# DM1098FFC_MIPI_CAM.net
KiCad netlist of a schematic drawn in Altium Designer
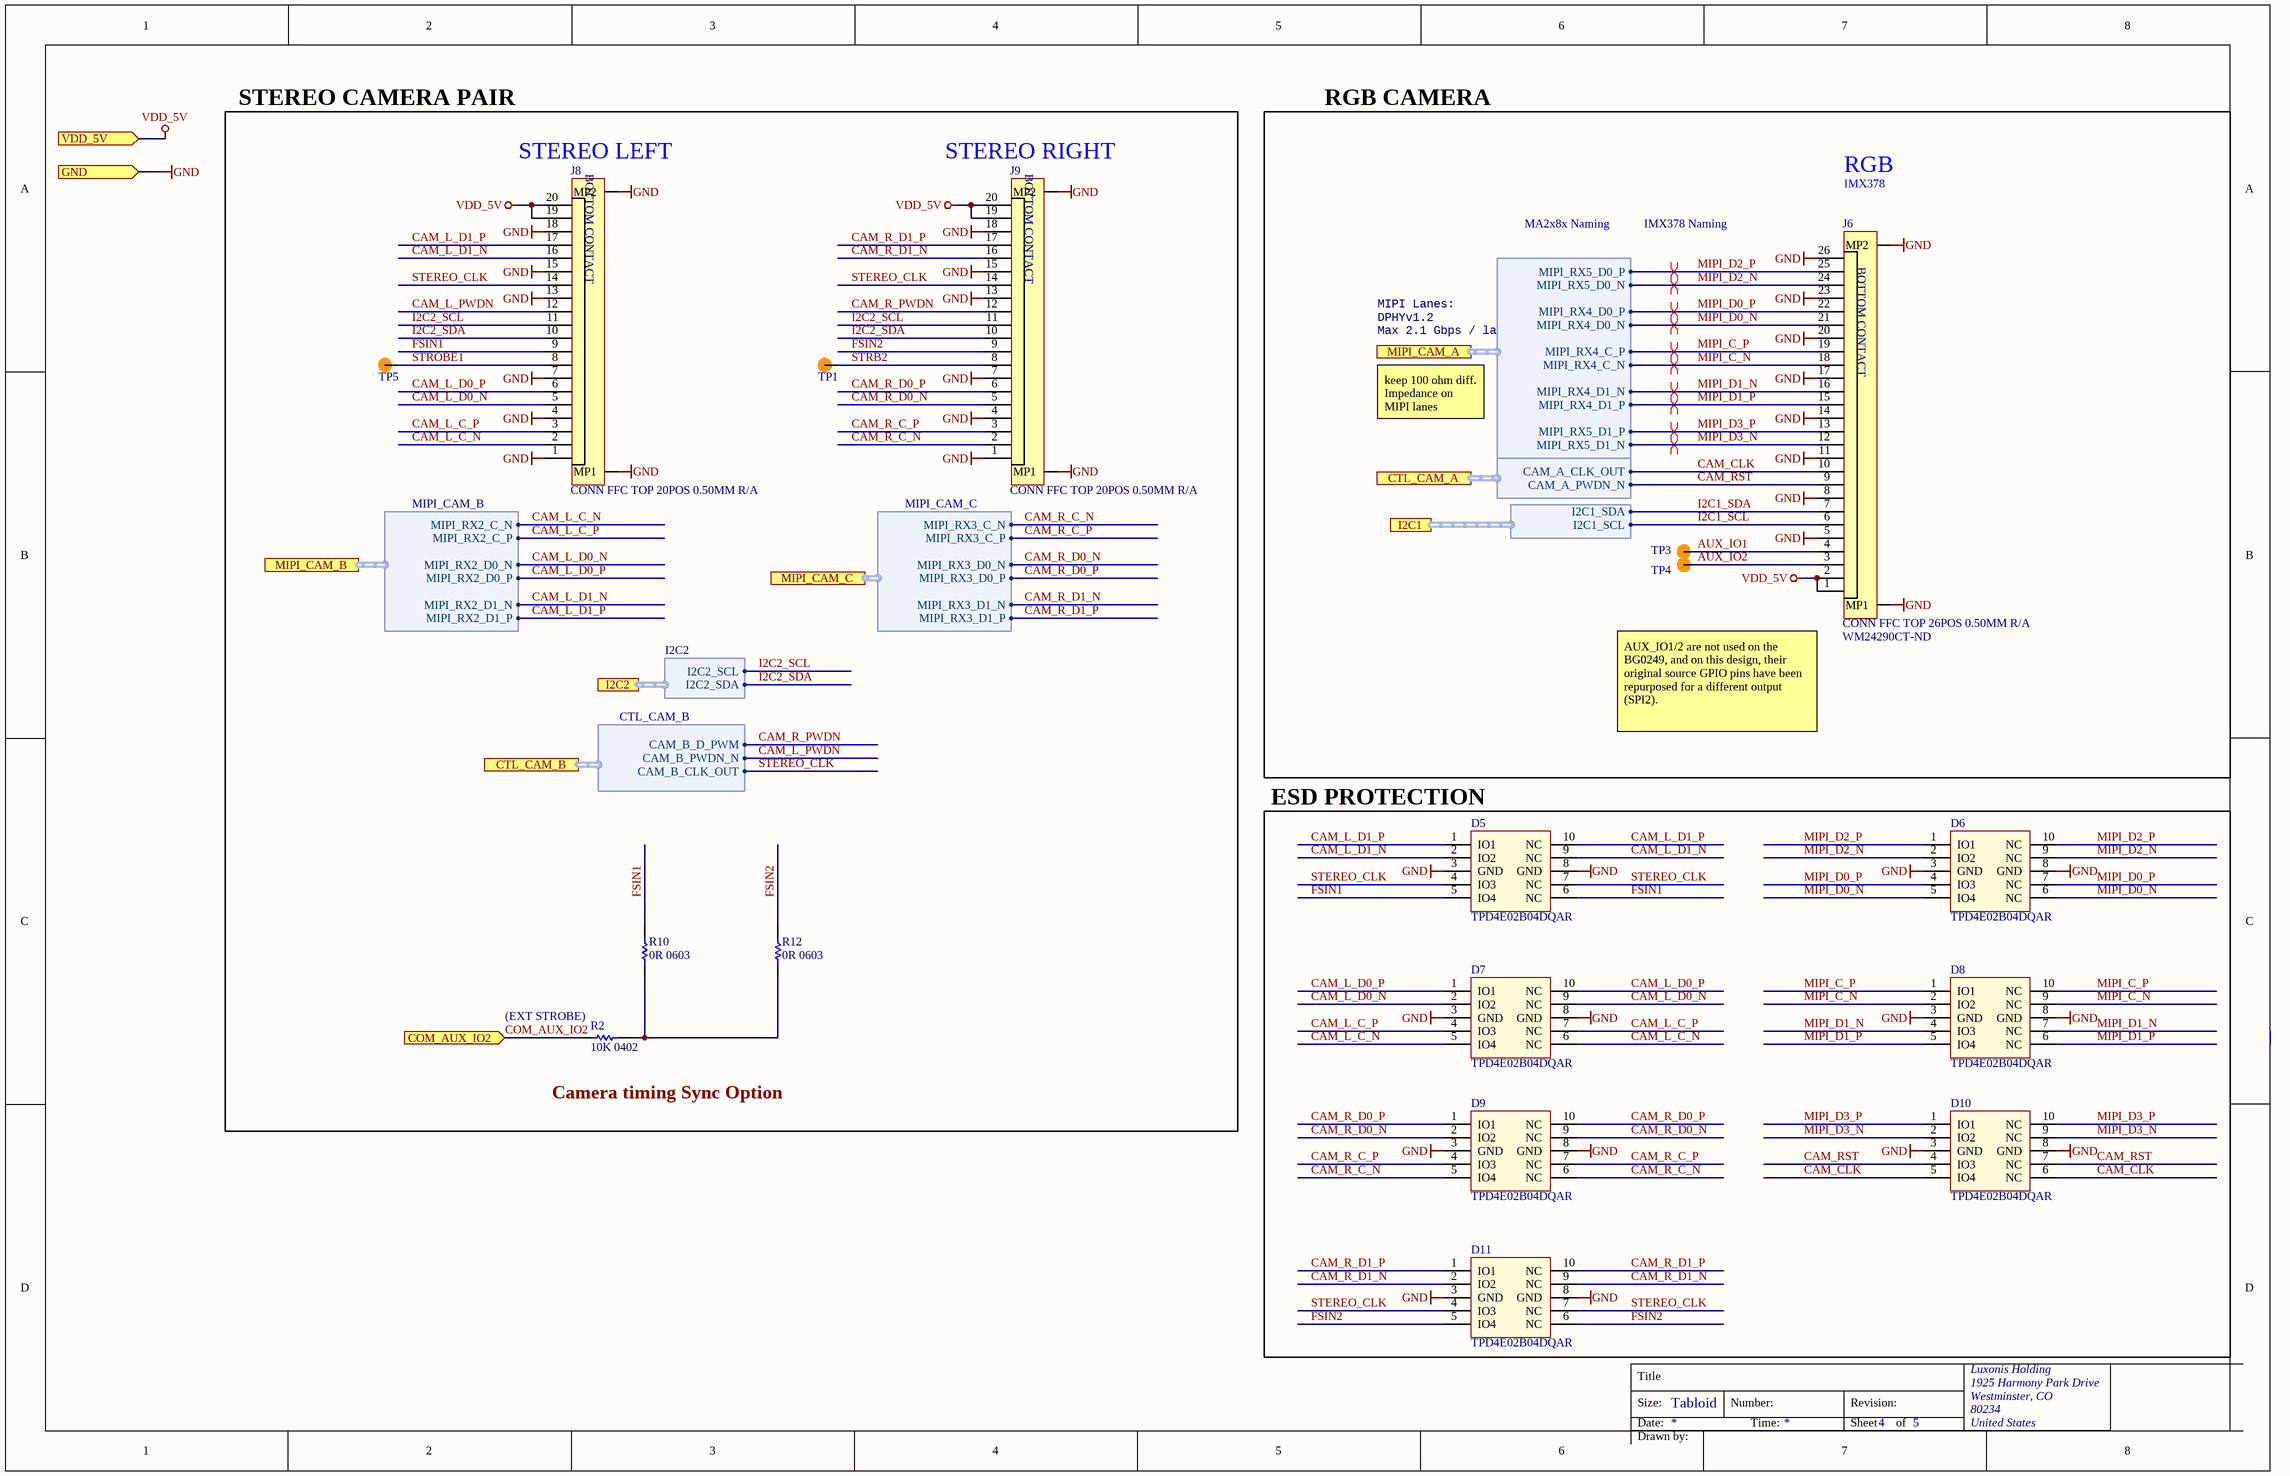
[diagram p0: DM1098FFC_MIPI_CAM.SchDoc]

(export (version "E")
  (design (tool "Eeschema 10.0.6"))
  (components
    (comp (ref "D5")
      (value "TPD4E02B04DQAR")
      (footprint "LuxonisMaster:TPD4E02B04DQAR")
      (libsource (lib "LuxonisMaster") (part "TPD4E02B04DQAR"))
    )
    (comp (ref "D6")
      (value "TPD4E02B04DQAR")
      (footprint "LuxonisMaster:TPD4E02B04DQAR")
      (libsource (lib "LuxonisMaster") (part "TPD4E02B04DQAR"))
    )
    (comp (ref "D7")
      (value "TPD4E02B04DQAR")
      (footprint "LuxonisMaster:TPD4E02B04DQAR")
      (libsource (lib "LuxonisMaster") (part "TPD4E02B04DQAR"))
    )
    (comp (ref "D8")
      (value "TPD4E02B04DQAR")
      (footprint "LuxonisMaster:TPD4E02B04DQAR")
      (libsource (lib "LuxonisMaster") (part "TPD4E02B04DQAR"))
    )
    (comp (ref "D9")
      (value "TPD4E02B04DQAR")
      (footprint "LuxonisMaster:TPD4E02B04DQAR")
      (libsource (lib "LuxonisMaster") (part "TPD4E02B04DQAR"))
    )
    (comp (ref "D10")
      (value "TPD4E02B04DQAR")
      (footprint "LuxonisMaster:TPD4E02B04DQAR")
      (libsource (lib "LuxonisMaster") (part "TPD4E02B04DQAR"))
    )
    (comp (ref "D11")
      (value "TPD4E02B04DQAR")
      (footprint "LuxonisMaster:TPD4E02B04DQAR")
      (libsource (lib "LuxonisMaster") (part "TPD4E02B04DQAR"))
    )
    (comp (ref "J6")
      (value "CONN FFC TOP 26POS 0.50MM R/A")
      (footprint "5052782633")
      (description "0.5 Ffc Zif Btm Cont Embt Pkg 0.5 Fpc Zif Btm FS19")
      (fields (field (name "SUPPLIER PART NUMBER 1") "WM24290CT-ND"))
      (libsource (lib "DM1098FFC") (part "5052782633"))
    )
    (comp (ref "J8")
      (value "CONN FFC TOP 20POS 0.50MM R/A")
      (footprint "5052782033")
      (description "0.5 Ffc Zif Btm Cont Embt Pkg 0.5 Fpc Zif Btm FS19")
      (libsource (lib "DM1098FFC") (part "5052782033"))
    )
    (comp (ref "J9")
      (value "CONN FFC TOP 20POS 0.50MM R/A")
      (footprint "5052782033")
      (description "0.5 Ffc Zif Btm Cont Embt Pkg 0.5 Fpc Zif Btm FS19")
      (libsource (lib "DM1098FFC") (part "5052782033"))
    )
    (comp (ref "R2")
      (value "10K 0402")
      (footprint "RES_Altium_Vault_Generic:RESC0402(1005)_N")
      (fields (field (name "TOLERANCE") "1%"))
      (libsource (lib "LuxonisMaster") (part "RC0402FR-1310KL"))
    )
    (comp (ref "R10")
      (value "0R 0603")
      (footprint "RES_Altium_Vault_Generic:RESC0603(1608)_N")
      (fields (field (name "TOLERANCE") "5%"))
      (libsource (lib "LuxonisMaster") (part "CRCW06030000Z0EA"))
    )
    (comp (ref "R12")
      (value "0R 0603")
      (footprint "RES_Altium_Vault_Generic:RESC0603(1608)_N")
      (fields (field (name "TOLERANCE") "5%"))
      (libsource (lib "LuxonisMaster") (part "CRCW06030000Z0EA"))
    )
    (comp (ref "TP1")
      (value "TP100_200_NS")
      (footprint "LuxonisMaster:TP100_200_NS")
      (libsource (lib "LuxonisMaster") (part "TEST_POINT"))
    )
    (comp (ref "TP3")
      (value "TP100_200_NS")
      (footprint "LuxonisMaster:TP100_200_NS")
      (libsource (lib "LuxonisMaster") (part "TEST_POINT"))
    )
    (comp (ref "TP4")
      (value "TP100_200_NS")
      (footprint "LuxonisMaster:TP100_200_NS")
      (libsource (lib "LuxonisMaster") (part "TEST_POINT"))
    )
    (comp (ref "TP5")
      (value "TP100_200_NS")
      (footprint "LuxonisMaster:TP100_200_NS")
      (libsource (lib "LuxonisMaster") (part "TEST_POINT"))
    )
  )
  (nets
    (net (code "8") (name "/AUX_IO1") (class "Default")
      (node (ref "J6") (pin "4") (pinfunction "4_4") (pintype "passive"))
      (node (ref "TP3") (pin "1") (pintype "passive"))
    )
    (net (code "9") (name "/AUX_IO2") (class "Default")
      (node (ref "J6") (pin "3") (pinfunction "3_3") (pintype "passive"))
      (node (ref "TP4") (pin "1") (pintype "passive"))
    )
    (net (code "10") (name "/CAM_CLK") (class "Default")
      (node (ref "D10") (pin "5") (pinfunction "IO4_5") (pintype "passive"))
      (node (ref "D10") (pin "6") (pinfunction "NC_6") (pintype "passive"))
      (node (ref "J6") (pin "10") (pinfunction "10_10") (pintype "passive"))
    )
    (net (code "11") (name "/CAM_L_C_N") (class "Default")
      (node (ref "D7") (pin "5") (pinfunction "IO4_5") (pintype "passive"))
      (node (ref "D7") (pin "6") (pinfunction "NC_6") (pintype "passive"))
      (node (ref "J8") (pin "2") (pinfunction "2_2") (pintype "passive"))
    )
    (net (code "12") (name "/CAM_L_C_P") (class "Default")
      (node (ref "D7") (pin "4") (pinfunction "IO3_4") (pintype "passive"))
      (node (ref "D7") (pin "7") (pinfunction "NC_7") (pintype "passive"))
      (node (ref "J8") (pin "3") (pinfunction "3_3") (pintype "passive"))
    )
    (net (code "13") (name "/CAM_L_D0_N") (class "Default")
      (node (ref "D7") (pin "2") (pinfunction "IO2_2") (pintype "passive"))
      (node (ref "D7") (pin "9") (pinfunction "NC_9") (pintype "passive"))
      (node (ref "J8") (pin "5") (pinfunction "5_5") (pintype "passive"))
    )
    (net (code "14") (name "/CAM_L_D0_P") (class "Default")
      (node (ref "D7") (pin "1") (pinfunction "IO1_1") (pintype "passive"))
      (node (ref "D7") (pin "10") (pinfunction "NC_10") (pintype "passive"))
      (node (ref "J8") (pin "6") (pinfunction "6_6") (pintype "passive"))
    )
    (net (code "15") (name "/CAM_L_D1_N") (class "Default")
      (node (ref "D5") (pin "2") (pinfunction "IO2_2") (pintype "passive"))
      (node (ref "D5") (pin "9") (pinfunction "NC_9") (pintype "passive"))
      (node (ref "J8") (pin "16") (pinfunction "16_16") (pintype "passive"))
    )
    (net (code "16") (name "/CAM_L_D1_P") (class "Default")
      (node (ref "D5") (pin "1") (pinfunction "IO1_1") (pintype "passive"))
      (node (ref "D5") (pin "10") (pinfunction "NC_10") (pintype "passive"))
      (node (ref "J8") (pin "17") (pinfunction "17_17") (pintype "passive"))
    )
    (net (code "17") (name "/CAM_L_PWDN") (class "Default")
      (node (ref "J8") (pin "12") (pinfunction "12_12") (pintype "passive"))
    )
    (net (code "18") (name "/CAM_RST") (class "Default")
      (node (ref "D10") (pin "4") (pinfunction "IO3_4") (pintype "passive"))
      (node (ref "D10") (pin "7") (pinfunction "NC_7") (pintype "passive"))
      (node (ref "J6") (pin "9") (pinfunction "9_9") (pintype "passive"))
    )
    (net (code "19") (name "/CAM_R_C_N") (class "Default")
      (node (ref "D9") (pin "5") (pinfunction "IO4_5") (pintype "passive"))
      (node (ref "D9") (pin "6") (pinfunction "NC_6") (pintype "passive"))
      (node (ref "J9") (pin "2") (pinfunction "2_2") (pintype "passive"))
    )
    (net (code "20") (name "/CAM_R_C_P") (class "Default")
      (node (ref "D9") (pin "4") (pinfunction "IO3_4") (pintype "passive"))
      (node (ref "D9") (pin "7") (pinfunction "NC_7") (pintype "passive"))
      (node (ref "J9") (pin "3") (pinfunction "3_3") (pintype "passive"))
    )
    (net (code "21") (name "/CAM_R_D0_N") (class "Default")
      (node (ref "D9") (pin "2") (pinfunction "IO2_2") (pintype "passive"))
      (node (ref "D9") (pin "9") (pinfunction "NC_9") (pintype "passive"))
      (node (ref "J9") (pin "5") (pinfunction "5_5") (pintype "passive"))
    )
    (net (code "22") (name "/CAM_R_D0_P") (class "Default")
      (node (ref "D9") (pin "1") (pinfunction "IO1_1") (pintype "passive"))
      (node (ref "D9") (pin "10") (pinfunction "NC_10") (pintype "passive"))
      (node (ref "J9") (pin "6") (pinfunction "6_6") (pintype "passive"))
    )
    (net (code "23") (name "/CAM_R_D1_N") (class "Default")
      (node (ref "D11") (pin "2") (pinfunction "IO2_2") (pintype "passive"))
      (node (ref "D11") (pin "9") (pinfunction "NC_9") (pintype "passive"))
      (node (ref "J9") (pin "16") (pinfunction "16_16") (pintype "passive"))
    )
    (net (code "24") (name "/CAM_R_D1_P") (class "Default")
      (node (ref "D11") (pin "1") (pinfunction "IO1_1") (pintype "passive"))
      (node (ref "D11") (pin "10") (pinfunction "NC_10") (pintype "passive"))
      (node (ref "J9") (pin "17") (pinfunction "17_17") (pintype "passive"))
    )
    (net (code "25") (name "/CAM_R_PWDN") (class "Default")
      (node (ref "J9") (pin "12") (pinfunction "12_12") (pintype "passive"))
    )
    (net (code "26") (name "/COM_AUX_IO2") (class "Default")
      (node (ref "R2") (pin "1") (pinfunction "1_1") (pintype "passive"))
    )
    (net (code "28") (name "/FSIN1") (class "Default")
      (node (ref "D5") (pin "5") (pinfunction "IO4_5") (pintype "passive"))
      (node (ref "D5") (pin "6") (pinfunction "NC_6") (pintype "passive"))
      (node (ref "J8") (pin "9") (pinfunction "9_9") (pintype "passive"))
      (node (ref "R10") (pin "2") (pinfunction "2_2") (pintype "passive"))
    )
    (net (code "29") (name "/FSIN2") (class "Default")
      (node (ref "D11") (pin "5") (pinfunction "IO4_5") (pintype "passive"))
      (node (ref "D11") (pin "6") (pinfunction "NC_6") (pintype "passive"))
      (node (ref "J9") (pin "9") (pinfunction "9_9") (pintype "passive"))
      (node (ref "R12") (pin "2") (pinfunction "2_2") (pintype "passive"))
    )
    (net (code "30") (name "/I2C1_SCL") (class "Default")
      (node (ref "J6") (pin "6") (pinfunction "6_6") (pintype "passive"))
    )
    (net (code "31") (name "/I2C1_SDA") (class "Default")
      (node (ref "J6") (pin "7") (pinfunction "7_7") (pintype "passive"))
    )
    (net (code "32") (name "/I2C2_SCL") (class "Default")
      (node (ref "J8") (pin "11") (pinfunction "11_11") (pintype "passive"))
      (node (ref "J9") (pin "11") (pinfunction "11_11") (pintype "passive"))
    )
    (net (code "33") (name "/I2C2_SDA") (class "Default")
      (node (ref "J8") (pin "10") (pinfunction "10_10") (pintype "passive"))
      (node (ref "J9") (pin "10") (pinfunction "10_10") (pintype "passive"))
    )
    (net (code "34") (name "/MIPI_C_N") (class "Default")
      (node (ref "D8") (pin "2") (pinfunction "IO2_2") (pintype "passive"))
      (node (ref "D8") (pin "9") (pinfunction "NC_9") (pintype "passive"))
      (node (ref "J6") (pin "18") (pinfunction "18_18") (pintype "passive"))
    )
    (net (code "35") (name "/MIPI_C_P") (class "Default")
      (node (ref "D8") (pin "1") (pinfunction "IO1_1") (pintype "passive"))
      (node (ref "D8") (pin "10") (pinfunction "NC_10") (pintype "passive"))
      (node (ref "J6") (pin "19") (pinfunction "19_19") (pintype "passive"))
    )
    (net (code "36") (name "/MIPI_D0_N") (class "Default")
      (node (ref "D6") (pin "5") (pinfunction "IO4_5") (pintype "passive"))
      (node (ref "D6") (pin "6") (pinfunction "NC_6") (pintype "passive"))
      (node (ref "J6") (pin "21") (pinfunction "21_21") (pintype "passive"))
    )
    (net (code "37") (name "/MIPI_D0_P") (class "Default")
      (node (ref "D6") (pin "4") (pinfunction "IO3_4") (pintype "passive"))
      (node (ref "D6") (pin "7") (pinfunction "NC_7") (pintype "passive"))
      (node (ref "J6") (pin "22") (pinfunction "22_22") (pintype "passive"))
    )
    (net (code "38") (name "/MIPI_D1_N") (class "Default")
      (node (ref "D8") (pin "4") (pinfunction "IO3_4") (pintype "passive"))
      (node (ref "D8") (pin "7") (pinfunction "NC_7") (pintype "passive"))
      (node (ref "J6") (pin "16") (pinfunction "16_16") (pintype "passive"))
    )
    (net (code "39") (name "/MIPI_D1_P") (class "Default")
      (node (ref "D8") (pin "5") (pinfunction "IO4_5") (pintype "passive"))
      (node (ref "D8") (pin "6") (pinfunction "NC_6") (pintype "passive"))
      (node (ref "J6") (pin "15") (pinfunction "15_15") (pintype "passive"))
    )
    (net (code "40") (name "/MIPI_D2_N") (class "Default")
      (node (ref "D6") (pin "2") (pinfunction "IO2_2") (pintype "passive"))
      (node (ref "D6") (pin "9") (pinfunction "NC_9") (pintype "passive"))
      (node (ref "J6") (pin "24") (pinfunction "24_24") (pintype "passive"))
    )
    (net (code "41") (name "/MIPI_D2_P") (class "Default")
      (node (ref "D6") (pin "1") (pinfunction "IO1_1") (pintype "passive"))
      (node (ref "D6") (pin "10") (pinfunction "NC_10") (pintype "passive"))
      (node (ref "J6") (pin "25") (pinfunction "25_25") (pintype "passive"))
    )
    (net (code "42") (name "/MIPI_D3_N") (class "Default")
      (node (ref "D10") (pin "2") (pinfunction "IO2_2") (pintype "passive"))
      (node (ref "D10") (pin "9") (pinfunction "NC_9") (pintype "passive"))
      (node (ref "J6") (pin "12") (pinfunction "12_12") (pintype "passive"))
    )
    (net (code "43") (name "/MIPI_D3_P") (class "Default")
      (node (ref "D10") (pin "1") (pinfunction "IO1_1") (pintype "passive"))
      (node (ref "D10") (pin "10") (pinfunction "NC_10") (pintype "passive"))
      (node (ref "J6") (pin "13") (pinfunction "13_13") (pintype "passive"))
    )
    (net (code "44") (name "/STEREO_CLK") (class "Default")
      (node (ref "D11") (pin "4") (pinfunction "IO3_4") (pintype "passive"))
      (node (ref "D11") (pin "7") (pinfunction "NC_7") (pintype "passive"))
      (node (ref "D5") (pin "4") (pinfunction "IO3_4") (pintype "passive"))
      (node (ref "D5") (pin "7") (pinfunction "NC_7") (pintype "passive"))
      (node (ref "J8") (pin "14") (pinfunction "14_14") (pintype "passive"))
      (node (ref "J9") (pin "14") (pinfunction "14_14") (pintype "passive"))
    )
    (net (code "45") (name "/STRB2") (class "Default")
      (node (ref "J9") (pin "8") (pinfunction "8_8") (pintype "passive"))
      (node (ref "TP1") (pin "1") (pintype "passive"))
    )
    (net (code "46") (name "/STROBE1") (class "Default")
      (node (ref "J8") (pin "8") (pinfunction "8_8") (pintype "passive"))
      (node (ref "TP5") (pin "1") (pintype "passive"))
    )
    (net (code "53") (name "GND") (class "Default")
      (node (ref "D10") (pin "3") (pinfunction "GND_3") (pintype "passive"))
      (node (ref "D10") (pin "8") (pinfunction "GND_8") (pintype "passive"))
      (node (ref "D11") (pin "3") (pinfunction "GND_3") (pintype "passive"))
      (node (ref "D11") (pin "8") (pinfunction "GND_8") (pintype "passive"))
      (node (ref "D5") (pin "3") (pinfunction "GND_3") (pintype "passive"))
      (node (ref "D5") (pin "8") (pinfunction "GND_8") (pintype "passive"))
      (node (ref "D6") (pin "3") (pinfunction "GND_3") (pintype "passive"))
      (node (ref "D6") (pin "8") (pinfunction "GND_8") (pintype "passive"))
      (node (ref "D7") (pin "3") (pinfunction "GND_3") (pintype "passive"))
      (node (ref "D7") (pin "8") (pinfunction "GND_8") (pintype "passive"))
      (node (ref "D8") (pin "3") (pinfunction "GND_3") (pintype "passive"))
      (node (ref "D8") (pin "8") (pinfunction "GND_8") (pintype "passive"))
      (node (ref "D9") (pin "3") (pinfunction "GND_3") (pintype "passive"))
      (node (ref "D9") (pin "8") (pinfunction "GND_8") (pintype "passive"))
      (node (ref "J6") (pin "11") (pinfunction "11_11") (pintype "passive"))
      (node (ref "J6") (pin "14") (pinfunction "14_14") (pintype "passive"))
      (node (ref "J6") (pin "17") (pinfunction "17_17") (pintype "passive"))
      (node (ref "J6") (pin "20") (pinfunction "20_20") (pintype "passive"))
      (node (ref "J6") (pin "23") (pinfunction "23_23") (pintype "passive"))
      (node (ref "J6") (pin "26") (pinfunction "26_26") (pintype "passive"))
      (node (ref "J6") (pin "5") (pinfunction "5_5") (pintype "passive"))
      (node (ref "J6") (pin "8") (pinfunction "8_8") (pintype "passive"))
      (node (ref "J6") (pin "MP1") (pinfunction "MP1_MP1") (pintype "passive"))
      (node (ref "J6") (pin "MP2") (pinfunction "MP2_MP2") (pintype "passive"))
      (node (ref "J8") (pin "1") (pinfunction "1_1") (pintype "passive"))
      (node (ref "J8") (pin "13") (pinfunction "13_13") (pintype "passive"))
      (node (ref "J8") (pin "15") (pinfunction "15_15") (pintype "passive"))
      (node (ref "J8") (pin "18") (pinfunction "18_18") (pintype "passive"))
      (node (ref "J8") (pin "4") (pinfunction "4_4") (pintype "passive"))
      (node (ref "J8") (pin "7") (pinfunction "7_7") (pintype "passive"))
      (node (ref "J8") (pin "MP1") (pinfunction "MP1_MP1") (pintype "passive"))
      (node (ref "J8") (pin "MP2") (pinfunction "MP2_MP2") (pintype "passive"))
      (node (ref "J9") (pin "1") (pinfunction "1_1") (pintype "passive"))
      (node (ref "J9") (pin "13") (pinfunction "13_13") (pintype "passive"))
      (node (ref "J9") (pin "15") (pinfunction "15_15") (pintype "passive"))
      (node (ref "J9") (pin "18") (pinfunction "18_18") (pintype "passive"))
      (node (ref "J9") (pin "4") (pinfunction "4_4") (pintype "passive"))
      (node (ref "J9") (pin "7") (pinfunction "7_7") (pintype "passive"))
      (node (ref "J9") (pin "MP1") (pinfunction "MP1_MP1") (pintype "passive"))
      (node (ref "J9") (pin "MP2") (pinfunction "MP2_MP2") (pintype "passive"))
    )
    (net (code "54") (name "Net-(R10-Pad1)") (class "Default")
      (node (ref "R10") (pin "1") (pinfunction "1_1") (pintype "passive"))
      (node (ref "R12") (pin "1") (pinfunction "1_1") (pintype "passive"))
      (node (ref "R2") (pin "2") (pinfunction "2_2") (pintype "passive"))
    )
    (net (code "55") (name "VDD_5V") (class "Default")
      (node (ref "J6") (pin "1") (pinfunction "1_1") (pintype "passive"))
      (node (ref "J6") (pin "2") (pinfunction "2_2") (pintype "passive"))
      (node (ref "J8") (pin "19") (pinfunction "19_19") (pintype "passive"))
      (node (ref "J8") (pin "20") (pinfunction "20_20") (pintype "passive"))
      (node (ref "J9") (pin "19") (pinfunction "19_19") (pintype "passive"))
      (node (ref "J9") (pin "20") (pinfunction "20_20") (pintype "passive"))
    )
  )
)
